# usb3_plug_to_picoblade.net
KiCad netlist of a schematic drawn in Altium Designer
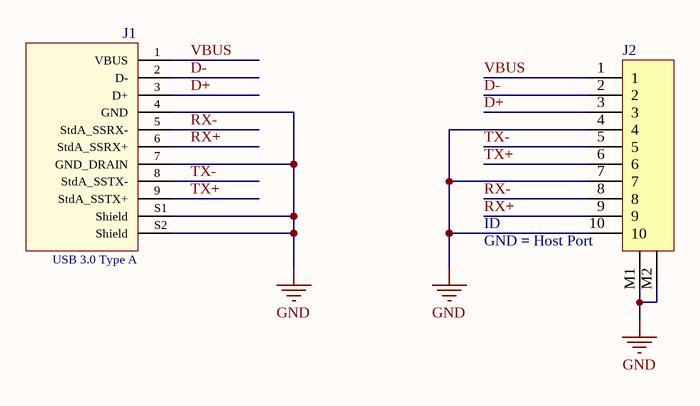
[diagram p0: usb3_plug_to_picoblade.SchDoc]

(export (version "E")
  (design (tool "Eeschema 10.0.6"))
  (components
    (comp (ref "J1")
      (value "USB 3.0 Type A")
      (footprint "692112030100")
      (description "USB 3.0 Type A Horizontal SMT Plug with Clip WR-COM")
      (fields (field (name "PART NUMBER") "692112030100") (field (name "PUBLISHER") "Wurth Elektronik"))
      (libsource (lib "ALTIUM-WR-COM-rev18a") (part "692112030100"))
    )
    (comp (ref "J2")
      (value "HEADER-10")
      (footprint "PICOBLADE-10-SMD")
      (libsource (lib "usb3_plug_to_picoblade") (part "PICOBLADE-10-SMD"))
    )
  )
  (nets
    (net (code "1") (name "/D+") (class "Default")
      (node (ref "J1") (pin "3") (pinfunction "D+_3") (pintype "passive"))
      (node (ref "J2") (pin "3") (pinfunction "3_3") (pintype "passive"))
    )
    (net (code "2") (name "/D-") (class "Default")
      (node (ref "J1") (pin "2") (pinfunction "D-_2") (pintype "passive"))
      (node (ref "J2") (pin "2") (pinfunction "2_2") (pintype "passive"))
    )
    (net (code "3") (name "/RX+") (class "Default")
      (node (ref "J1") (pin "6") (pinfunction "StdA_SSRX+_6") (pintype "passive"))
      (node (ref "J2") (pin "9") (pinfunction "9_9") (pintype "passive"))
    )
    (net (code "4") (name "/RX-") (class "Default")
      (node (ref "J1") (pin "5") (pinfunction "StdA_SSRX-_5") (pintype "passive"))
      (node (ref "J2") (pin "8") (pinfunction "8_8") (pintype "passive"))
    )
    (net (code "5") (name "/TX+") (class "Default")
      (node (ref "J1") (pin "9") (pinfunction "StdA_SSTX+_9") (pintype "passive"))
      (node (ref "J2") (pin "6") (pinfunction "6_6") (pintype "passive"))
    )
    (net (code "6") (name "/TX-") (class "Default")
      (node (ref "J1") (pin "8") (pinfunction "StdA_SSTX-_8") (pintype "passive"))
      (node (ref "J2") (pin "5") (pinfunction "5_5") (pintype "passive"))
    )
    (net (code "7") (name "/VBUS") (class "Default")
      (node (ref "J1") (pin "1") (pinfunction "VBUS_1") (pintype "passive"))
      (node (ref "J2") (pin "1") (pinfunction "1_1") (pintype "passive"))
    )
    (net (code "8") (name "GND") (class "Default")
      (node (ref "J1") (pin "4") (pinfunction "GND_4") (pintype "passive"))
      (node (ref "J1") (pin "7") (pinfunction "GND_DRAIN_7") (pintype "passive"))
      (node (ref "J1") (pin "S1") (pinfunction "Shield_S1") (pintype "passive"))
      (node (ref "J1") (pin "S2") (pinfunction "Shield_S2") (pintype "passive"))
      (node (ref "J2") (pin "10") (pinfunction "10_10") (pintype "passive"))
      (node (ref "J2") (pin "4") (pinfunction "4_4") (pintype "passive"))
      (node (ref "J2") (pin "7") (pinfunction "7_7") (pintype "passive"))
      (node (ref "J2") (pin "M1") (pinfunction "M2_M1") (pintype "passive"))
      (node (ref "J2") (pin "M2") (pinfunction "M2_M2") (pintype "passive"))
    )
  )
)
